# sch_imge.net
KiCad netlist of a schematic drawn in Altium Designer
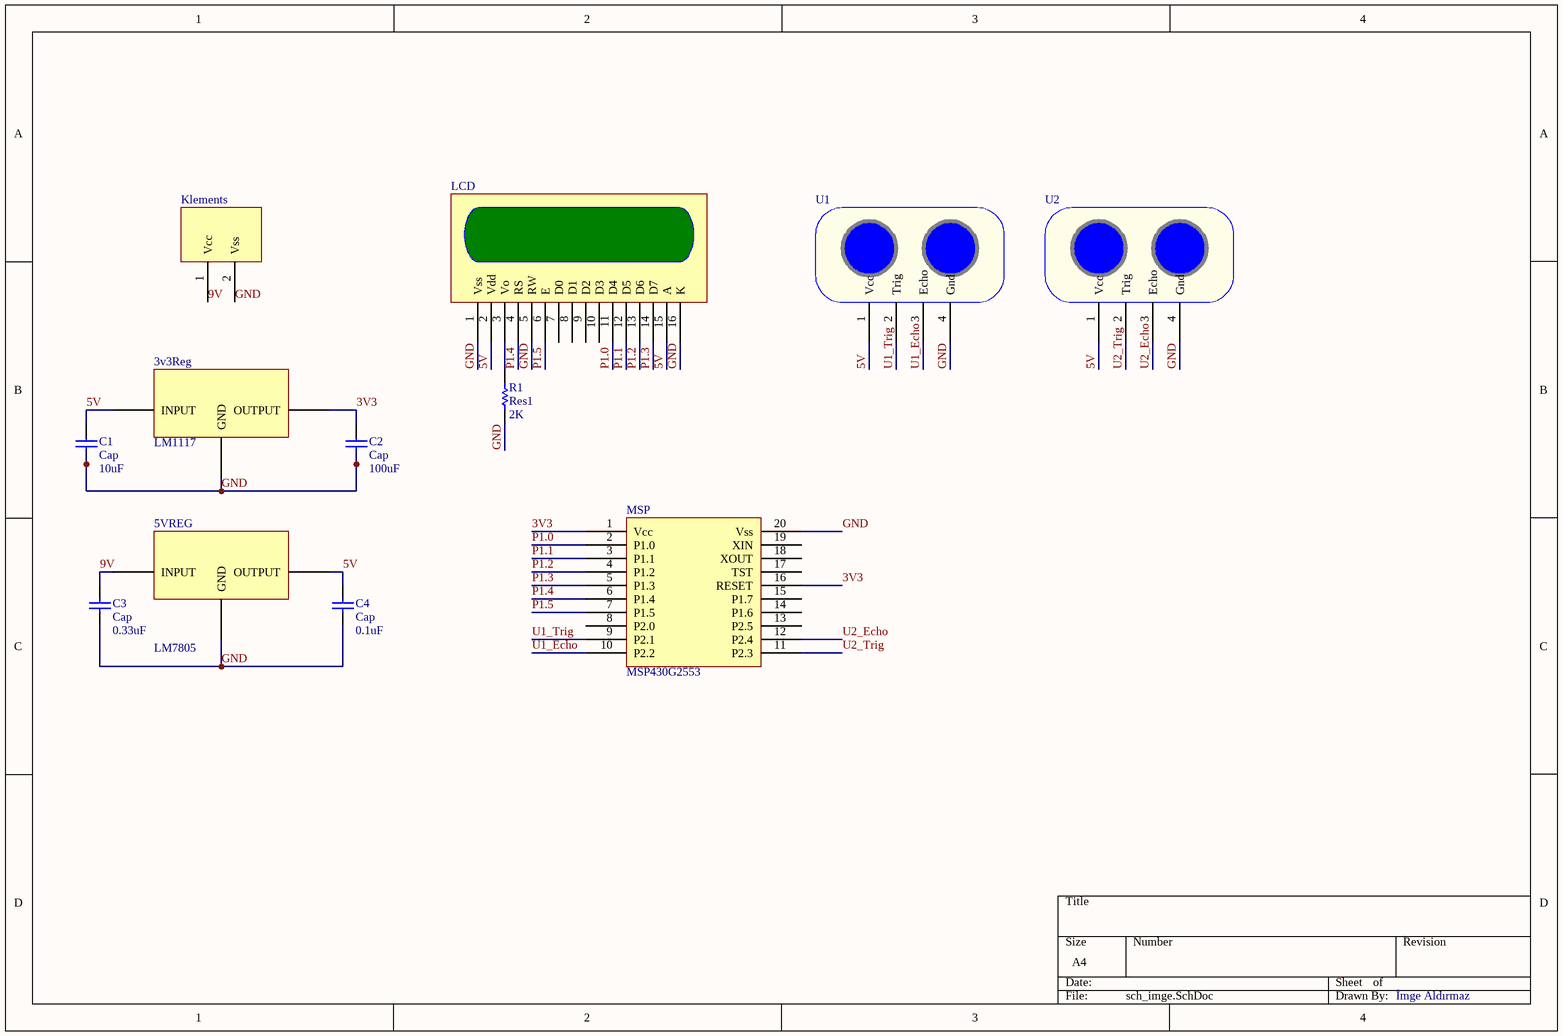
[diagram p0: sch_imge.SchDoc]

(export (version "E")
  (design (tool "Eeschema 10.0.6"))
  (components
    (comp (ref "3v3Reg") (value "LM1117") (footprint "3v3_Reg_") (libsource (lib "myLib") (part "LM1117")))
    (comp (ref "5VREG") (value "LM7805") (footprint "5V_REG") (libsource (lib "myLib") (part "LM7805")))
    (comp (ref "C1")
      (value "Cap")
      (footprint "RAD-0.3")
      (description "Capacitor")
      (fields (field (name "ALTIUM_VALUE") "10uF") (field (name "PUBLISHER") "Altium Limited"))
      (libsource (lib "Miscellaneous Devices") (part "Cap"))
    )
    (comp (ref "C2")
      (value "Cap")
      (footprint "RAD-0.3")
      (description "Capacitor")
      (fields (field (name "ALTIUM_VALUE") "100uF") (field (name "PUBLISHER") "Altium Limited"))
      (libsource (lib "Miscellaneous Devices") (part "Cap"))
    )
    (comp (ref "C3")
      (value "Cap")
      (footprint "RAD-0.3")
      (description "Capacitor")
      (fields (field (name "ALTIUM_VALUE") "0.33uF") (field (name "PUBLISHER") "Altium Limited"))
      (libsource (lib "Miscellaneous Devices") (part "Cap"))
    )
    (comp (ref "C4")
      (value "Cap")
      (footprint "RAD-0.3")
      (description "Capacitor")
      (fields (field (name "ALTIUM_VALUE") "0.1uF") (field (name "PUBLISHER") "Altium Limited"))
      (libsource (lib "Miscellaneous Devices") (part "Cap"))
    )
    (comp (ref "K") (value "Klements") (footprint "Klements") (libsource (lib "myLib") (part "Klements")))
    (comp (ref "LCD") (value "LCD") (footprint "LCD") (libsource (lib "myLib") (part "LCD")))
    (comp (ref "MSP")
      (value "MSP430G2553")
      (footprint "MSP430G2553_FP")
      (libsource (lib "myLib") (part "MSP430G2553"))
    )
    (comp (ref "R1")
      (value "Res1")
      (footprint "AXIAL-0.3")
      (description "Resistor")
      (fields (field (name "ALTIUM_VALUE") "2K") (field (name "PUBLISHER") "Altium Limited"))
      (libsource (lib "Miscellaneous Devices") (part "Res1"))
    )
    (comp (ref "U1")
      (value "Ultrasonic")
      (footprint "Ultasonik_FP")
      (libsource (lib "myLib") (part "Ultrasonic"))
    )
    (comp (ref "U2")
      (value "Ultrasonic")
      (footprint "Ultasonik_FP")
      (libsource (lib "myLib") (part "Ultrasonic"))
    )
  )
  (nets
    (net (code "1") (name "/3V3") (class "Default")
      (node (ref "3v3Reg") (pin "1") (pinfunction "OUTPUT_1") (pintype "passive"))
      (node (ref "C2") (pin "2") (pinfunction "2_2") (pintype "passive"))
      (node (ref "MSP") (pin "1") (pinfunction "Vcc_1") (pintype "passive"))
      (node (ref "MSP") (pin "16") (pinfunction "RESET_16") (pintype "passive"))
    )
    (net (code "2") (name "/5V") (class "Default")
      (node (ref "3v3Reg") (pin "2") (pinfunction "INPUT_2") (pintype "passive"))
      (node (ref "5VREG") (pin "2") (pinfunction "OUTPUT_2") (pintype "passive"))
      (node (ref "C1") (pin "2") (pinfunction "2_2") (pintype "passive"))
      (node (ref "C4") (pin "2") (pinfunction "2_2") (pintype "passive"))
      (node (ref "LCD") (pin "15") (pinfunction "A_15") (pintype "passive"))
      (node (ref "LCD") (pin "2") (pinfunction "Vdd_2") (pintype "passive"))
      (node (ref "U1") (pin "1") (pinfunction "Vcc_1") (pintype "passive"))
      (node (ref "U2") (pin "1") (pinfunction "Vcc_1") (pintype "passive"))
    )
    (net (code "3") (name "/9V") (class "Default")
      (node (ref "5VREG") (pin "0") (pinfunction "INPUT_0") (pintype "passive"))
      (node (ref "C3") (pin "2") (pinfunction "2_2") (pintype "passive"))
      (node (ref "K") (pin "1") (pinfunction "Vcc_1") (pintype "passive"))
    )
    (net (code "4") (name "/GND") (class "Default")
      (node (ref "3v3Reg") (pin "0") (pinfunction "GND_0") (pintype "passive"))
      (node (ref "5VREG") (pin "1") (pinfunction "GND_1") (pintype "passive"))
      (node (ref "C1") (pin "1") (pinfunction "1_1") (pintype "passive"))
      (node (ref "C2") (pin "1") (pinfunction "1_1") (pintype "passive"))
      (node (ref "C3") (pin "1") (pinfunction "1_1") (pintype "passive"))
      (node (ref "C4") (pin "1") (pinfunction "1_1") (pintype "passive"))
      (node (ref "K") (pin "2") (pinfunction "Vss_2") (pintype "passive"))
      (node (ref "LCD") (pin "1") (pinfunction "Vss_1") (pintype "passive"))
      (node (ref "LCD") (pin "16") (pinfunction "K_16") (pintype "passive"))
      (node (ref "LCD") (pin "5") (pinfunction "RW_5") (pintype "passive"))
      (node (ref "MSP") (pin "20") (pinfunction "Vss_20") (pintype "passive"))
      (node (ref "R1") (pin "1") (pinfunction "1_1") (pintype "passive"))
      (node (ref "U1") (pin "4") (pinfunction "Gnd_4") (pintype "passive"))
      (node (ref "U2") (pin "4") (pinfunction "Gnd_4") (pintype "passive"))
    )
    (net (code "5") (name "/P1.0") (class "Default")
      (node (ref "LCD") (pin "11") (pinfunction "D4_11") (pintype "passive"))
      (node (ref "MSP") (pin "2") (pinfunction "P1.0_2") (pintype "passive"))
    )
    (net (code "6") (name "/P1.1") (class "Default")
      (node (ref "LCD") (pin "12") (pinfunction "D5_12") (pintype "passive"))
      (node (ref "MSP") (pin "3") (pinfunction "P1.1_3") (pintype "passive"))
    )
    (net (code "7") (name "/P1.2") (class "Default")
      (node (ref "LCD") (pin "13") (pinfunction "D6_13") (pintype "passive"))
      (node (ref "MSP") (pin "4") (pinfunction "P1.2_4") (pintype "passive"))
    )
    (net (code "8") (name "/P1.3") (class "Default")
      (node (ref "LCD") (pin "14") (pinfunction "D7_14") (pintype "passive"))
      (node (ref "MSP") (pin "5") (pinfunction "P1.3_5") (pintype "passive"))
    )
    (net (code "9") (name "/P1.4") (class "Default")
      (node (ref "LCD") (pin "4") (pinfunction "RS_4") (pintype "passive"))
      (node (ref "MSP") (pin "6") (pinfunction "P1.4_6") (pintype "passive"))
    )
    (net (code "10") (name "/P1.5") (class "Default")
      (node (ref "LCD") (pin "6") (pinfunction "E_6") (pintype "passive"))
      (node (ref "MSP") (pin "7") (pinfunction "P1.5_7") (pintype "passive"))
    )
    (net (code "11") (name "/U1_Echo") (class "Default")
      (node (ref "MSP") (pin "10") (pinfunction "P2.2_10") (pintype "passive"))
      (node (ref "U1") (pin "3") (pinfunction "Echo_3") (pintype "passive"))
    )
    (net (code "12") (name "/U1_Trig") (class "Default")
      (node (ref "MSP") (pin "9") (pinfunction "P2.1_9") (pintype "passive"))
      (node (ref "U1") (pin "2") (pinfunction "Trig_2") (pintype "passive"))
    )
    (net (code "13") (name "/U2_Echo") (class "Default")
      (node (ref "MSP") (pin "12") (pinfunction "P2.4_12") (pintype "passive"))
      (node (ref "U2") (pin "3") (pinfunction "Echo_3") (pintype "passive"))
    )
    (net (code "14") (name "/U2_Trig") (class "Default")
      (node (ref "MSP") (pin "11") (pinfunction "P2.3_11") (pintype "passive"))
      (node (ref "U2") (pin "2") (pinfunction "Trig_2") (pintype "passive"))
    )
    (net (code "15") (name "Net-(LCD-Vo)") (class "Default")
      (node (ref "LCD") (pin "3") (pinfunction "Vo_3") (pintype "passive"))
      (node (ref "R1") (pin "2") (pinfunction "2_2") (pintype "passive"))
    )
    (net (code "16") (name "unconnected-(LCD-D0-Pad7)") (class "Default")
      (node (ref "LCD") (pin "7") (pinfunction "D0_7") (pintype "passive"))
    )
    (net (code "17") (name "unconnected-(LCD-D1-Pad8)") (class "Default")
      (node (ref "LCD") (pin "8") (pinfunction "D1_8") (pintype "passive"))
    )
    (net (code "18") (name "unconnected-(LCD-D2-Pad9)") (class "Default")
      (node (ref "LCD") (pin "9") (pinfunction "D2_9") (pintype "passive"))
    )
    (net (code "19") (name "unconnected-(LCD-D3-Pad10)") (class "Default")
      (node (ref "LCD") (pin "10") (pinfunction "D3_10") (pintype "passive"))
    )
    (net (code "20") (name "unconnected-(MSP-P1.6-Pad14)") (class "Default")
      (node (ref "MSP") (pin "14") (pinfunction "P1.6_14") (pintype "passive"))
    )
    (net (code "21") (name "unconnected-(MSP-P1.7-Pad15)") (class "Default")
      (node (ref "MSP") (pin "15") (pinfunction "P1.7_15") (pintype "passive"))
    )
    (net (code "22") (name "unconnected-(MSP-P2.0-Pad8)") (class "Default")
      (node (ref "MSP") (pin "8") (pinfunction "P2.0_8") (pintype "passive"))
    )
    (net (code "23") (name "unconnected-(MSP-P2.5-Pad13)") (class "Default")
      (node (ref "MSP") (pin "13") (pinfunction "P2.5_13") (pintype "passive"))
    )
    (net (code "24") (name "unconnected-(MSP-TST-Pad17)") (class "Default")
      (node (ref "MSP") (pin "17") (pinfunction "TST_17") (pintype "passive"))
    )
    (net (code "25") (name "unconnected-(MSP-XIN-Pad19)") (class "Default")
      (node (ref "MSP") (pin "19") (pinfunction "XIN_19") (pintype "passive"))
    )
    (net (code "26") (name "unconnected-(MSP-XOUT-Pad18)") (class "Default")
      (node (ref "MSP") (pin "18") (pinfunction "XOUT_18") (pintype "passive"))
    )
  )
)
